# Main.net
KiCad netlist of a schematic drawn in Altium Designer
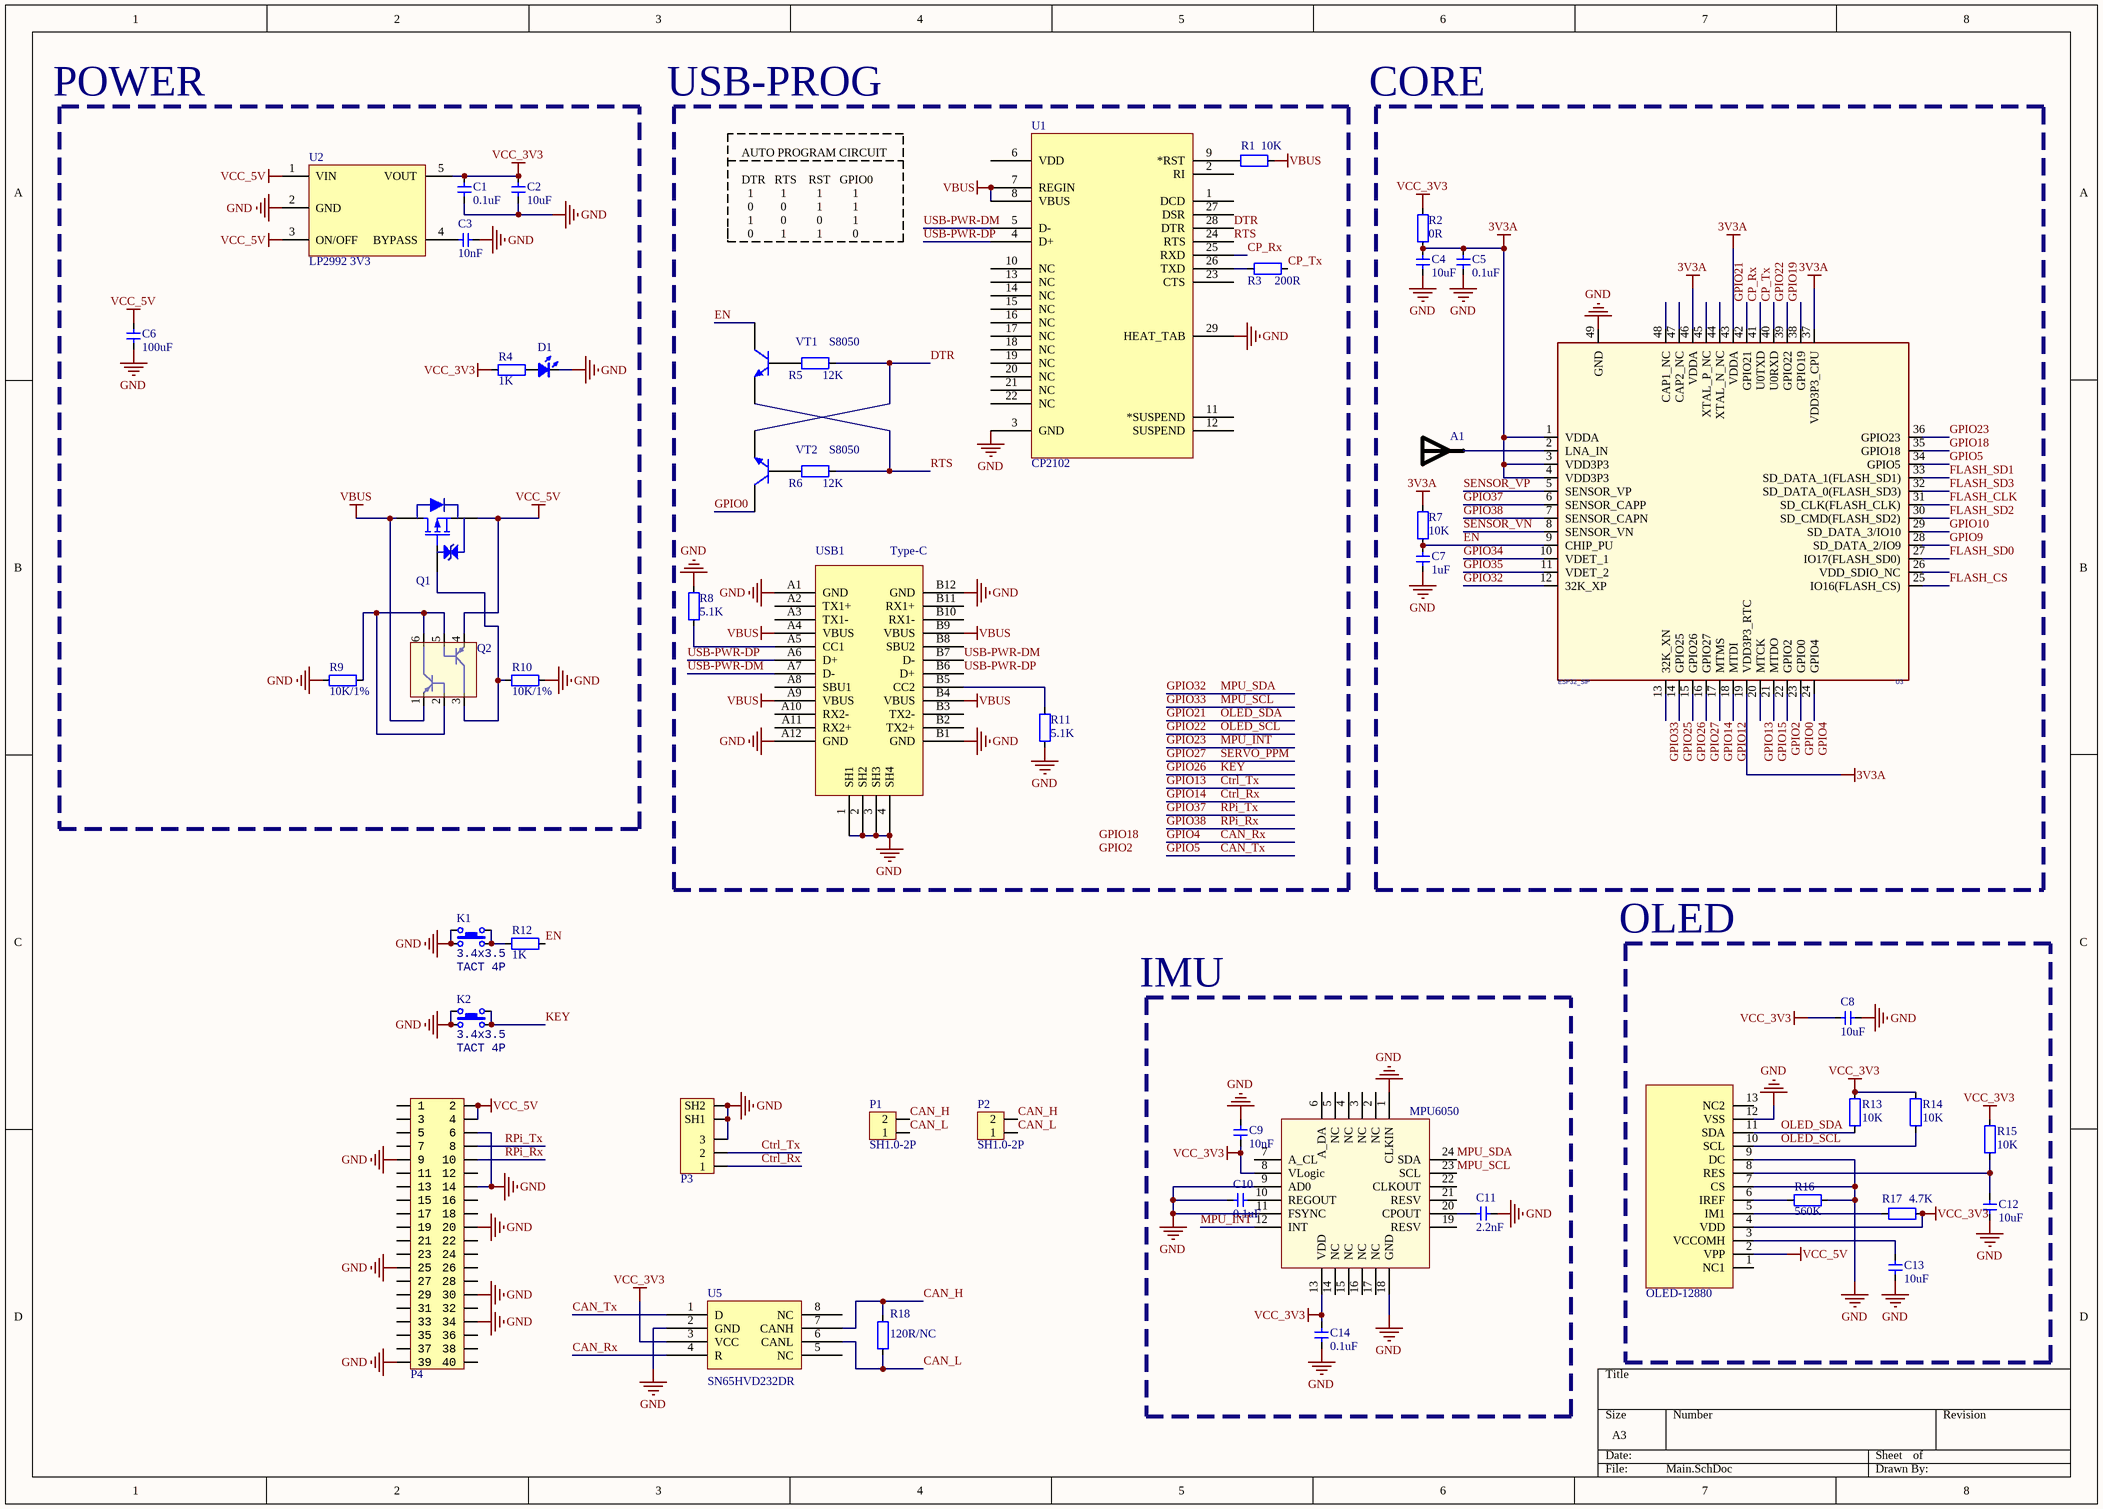
[diagram p0: Main.SchDoc]

(export (version "E")
  (design (tool "Eeschema 10.0.6"))
  (components
    (comp (ref "1")
      (value "OLED-12880")
      (footprint "OLED-12880")
      (libsource (lib "mLib") (part "OLED-12880"))
    )
    (comp (ref "A1")
      (value "RAINSUN")
      (footprint "ANT-Rainsun-AN5120")
      (libsource (lib "MyPcbLib") (part "ANT-Rainsun-AP5120"))
    )
    (comp (ref "C1")
      (value "0.1uF")
      (footprint "CAP_0402")
      (description "Capacitor")
      (libsource (lib "MyPcbLib") (part "电容-0402"))
    )
    (comp (ref "C2")
      (value "10uF")
      (footprint "CAP_0402")
      (description "Capacitor")
      (libsource (lib "MyPcbLib") (part "电容-0402"))
    )
    (comp (ref "C3")
      (value "10nF")
      (footprint "CAP_0402")
      (description "Capacitor")
      (libsource (lib "MyPcbLib") (part "电容-0402"))
    )
    (comp (ref "C4")
      (value "10uF")
      (footprint "CAP_0402")
      (description "Capacitor")
      (libsource (lib "MyPcbLib") (part "电容-0402"))
    )
    (comp (ref "C5")
      (value "0.1uF")
      (footprint "CAP_0402")
      (description "Capacitor")
      (libsource (lib "MyPcbLib") (part "电容-0402"))
    )
    (comp (ref "C6")
      (value "100uF")
      (footprint "1206-CAP")
      (description "Capacitor")
      (libsource (lib "MyPcbLib") (part "电容-1206"))
    )
    (comp (ref "C7")
      (value "1uF")
      (footprint "CAP_0402")
      (description "Capacitor")
      (libsource (lib "MyPcbLib") (part "电容-0402"))
    )
    (comp (ref "C8")
      (value "10uF")
      (footprint "CAP_0402")
      (description "Capacitor")
      (libsource (lib "MyPcbLib") (part "电容-0402"))
    )
    (comp (ref "C9")
      (value "10nF")
      (footprint "CAP_0402")
      (description "Capacitor")
      (libsource (lib "MyPcbLib") (part "电容-0402"))
    )
    (comp (ref "C10")
      (value "0.1uF")
      (footprint "CAP_0402")
      (description "Capacitor")
      (libsource (lib "MyPcbLib") (part "电容-0402"))
    )
    (comp (ref "C11")
      (value "2.2nF")
      (footprint "CAP_0402")
      (description "Capacitor")
      (libsource (lib "MyPcbLib") (part "电容-0402"))
    )
    (comp (ref "C12")
      (value "10uF")
      (footprint "CAP_0402")
      (description "Capacitor")
      (libsource (lib "MyPcbLib") (part "电容-0402"))
    )
    (comp (ref "C13")
      (value "10uF")
      (footprint "CAP_0402")
      (description "Capacitor")
      (libsource (lib "MyPcbLib") (part "电容-0402"))
    )
    (comp (ref "C14")
      (value "0.1uF")
      (footprint "CAP_0402")
      (description "Capacitor")
      (libsource (lib "MyPcbLib") (part "电容-0402"))
    )
    (comp (ref "D1")
      (value "color?")
      (footprint "LED_0402_RED")
      (description "LED")
      (libsource (lib "KitSprout") (part "LED_0402"))
    )
    (comp (ref "K1")
      (value "3.4x3.5")
      (footprint "ButtonTACT_3.5*3.55_90")
      (description "Button")
      (fields (field (name "TYPE") "TACT 4P") (field (name "Comment") "TACT 4P"))
      (libsource (lib "KitSprout") (part "ButtonTACT"))
    )
    (comp (ref "K2")
      (value "3.4x3.5")
      (footprint "ButtonTACT_3.5*3.55_90")
      (description "Button")
      (fields (field (name "TYPE") "TACT 4P") (field (name "Comment") "TACT 4P"))
      (libsource (lib "KitSprout") (part "ButtonTACT"))
    )
    (comp (ref "P1") (value "SH1.0-2P") (footprint "SH1.0-2P") (libsource (lib "MyPcbLib") (part "SH1.0-2P")))
    (comp (ref "P2") (value "SH1.0-2P") (footprint "SH1.0-2P") (libsource (lib "MyPcbLib") (part "SH1.0-2P")))
    (comp (ref "P3")
      (value "SH1.0-3P")
      (footprint "SH1.0-3P")
      (description "Header")
      (libsource (lib "MyPcbLib") (part "SH1.0-3P"))
    )
    (comp (ref "P4")
      (value "HDR2x20_2.54")
      (footprint "HDR2X20_2.54_180F")
      (description "Header")
      (libsource (lib "KitSprout") (part "HDR2x20_2.54"))
    )
    (comp (ref "Q1")
      (value "AO3415A")
      (footprint "SOT23-3")
      (description "MOSFET")
      (fields (field (name "PUBLISHER") "Altium Limited"))
      (libsource (lib "MyPcbLib") (part "AO3415A"))
    )
    (comp (ref "Q2")
      (value "BCM856BS")
      (footprint "SOT363-6")
      (description "Transistor")
      (libsource (lib "MyPcbLib") (part "BCM856BS"))
    )
    (comp (ref "R1")
      (value "10K")
      (footprint "RES_0402")
      (description "Resistor")
      (libsource (lib "") (part "电阻-0402_3"))
    )
    (comp (ref "R2")
      (value "0R")
      (footprint "RES_0402")
      (description "Resistor")
      (libsource (lib "") (part "电阻-0402_2"))
    )
    (comp (ref "R3")
      (value "200R")
      (footprint "RES_0402")
      (description "Resistor")
      (libsource (lib "") (part "电阻-0402_3"))
    )
    (comp (ref "R4")
      (value "1K")
      (footprint "RES_0402")
      (description "Resistor")
      (libsource (lib "") (part "电阻-0402_1"))
    )
    (comp (ref "R5")
      (value "12K")
      (footprint "RES_0402")
      (description "Resistor")
      (libsource (lib "") (part "电阻-0402_3"))
    )
    (comp (ref "R6")
      (value "12K")
      (footprint "RES_0402")
      (description "Resistor")
      (libsource (lib "") (part "电阻-0402_3"))
    )
    (comp (ref "R7")
      (value "10K")
      (footprint "RES_0402")
      (description "Resistor")
      (libsource (lib "") (part "电阻-0402_2"))
    )
    (comp (ref "R8")
      (value "5.1K")
      (footprint "RES_0402")
      (description "Resistor")
      (libsource (lib "") (part "电阻-0402_2"))
    )
    (comp (ref "R9")
      (value "10K/1%")
      (footprint "RES_0402")
      (description "Resistor")
      (libsource (lib "") (part "电阻-0402_1"))
    )
    (comp (ref "R10")
      (value "10K/1%")
      (footprint "RES_0402")
      (description "Resistor")
      (libsource (lib "") (part "电阻-0402_1"))
    )
    (comp (ref "R11")
      (value "5.1K")
      (footprint "RES_0402")
      (description "Resistor")
      (libsource (lib "MyPcbLib") (part "电阻-0402"))
    )
    (comp (ref "R12")
      (value "1K")
      (footprint "RES_0402")
      (description "Resistor")
      (libsource (lib "") (part "电阻-0402_1"))
    )
    (comp (ref "R13")
      (value "10K")
      (footprint "RES_0402")
      (description "Resistor")
      (libsource (lib "MyPcbLib") (part "电阻-0402"))
    )
    (comp (ref "R14")
      (value "10K")
      (footprint "RES_0402")
      (description "Resistor")
      (libsource (lib "MyPcbLib") (part "电阻-0402"))
    )
    (comp (ref "R15")
      (value "10K")
      (footprint "RES_0402")
      (description "Resistor")
      (libsource (lib "MyPcbLib") (part "电阻-0402"))
    )
    (comp (ref "R16")
      (value "560K")
      (footprint "RES_0402")
      (description "Resistor")
      (libsource (lib "") (part "电阻-0402_1"))
    )
    (comp (ref "R17")
      (value "4.7K")
      (footprint "RES_0402")
      (description "Resistor")
      (libsource (lib "") (part "电阻-0402_1"))
    )
    (comp (ref "R18")
      (value "120R/NC")
      (footprint "RES_0402")
      (description "Resistor")
      (libsource (lib "") (part "电阻-0402_2"))
    )
    (comp (ref "U1")
      (value "CP2102")
      (footprint "QFN-28")
      (description "USB转TTL")
      (libsource (lib "mLib") (part "CP2102"))
    )
    (comp (ref "U2")
      (value "LP2992 3V3")
      (footprint "SOT23-5")
      (description "LDO")
      (libsource (lib "MyPcbLib") (part "LP2992"))
    )
    (comp (ref "U3")
      (value "ESP32_SIP")
      (footprint "QFN-48_7X7")
      (libsource (lib "MyPcbLib") (part "ESP32-PICO"))
    )
    (comp (ref "U4")
      (value "MPU6050")
      (footprint "QFN-24")
      (description "六轴传感器")
      (libsource (lib "mLib") (part "MPU6050"))
    )
    (comp (ref "U5")
      (value "SN65HVD232D")
      (footprint "SO-8")
      (fields
        (field (name "MANUFACTURER") "Texas Instruments")
        (field (name "MANUFACTURER PART NUMBER") "SN65HVD232DR")
      )
      (libsource (lib "MyPcbLib") (part "SN65HVD232D"))
    )
    (comp (ref "USB1")
      (value "Type-C")
      (footprint "Type-C-TOP")
      (libsource (lib "MyPcbLib") (part "USB-Type-C-TOP"))
    )
    (comp (ref "VT1")
      (value "S8050")
      (footprint "SMT_TRIODE_NPN")
      (description "Surface mount NPN transistor, package SOT-23")
      (libsource (lib "MyPcbLib") (part "SMT_TRIODE_NPN"))
    )
    (comp (ref "VT2")
      (value "S8050")
      (footprint "SMT_TRIODE_NPN")
      (description "Surface mount NPN transistor, package SOT-23")
      (libsource (lib "MyPcbLib") (part "SMT_TRIODE_NPN"))
    )
  )
  (nets
    (net (code "1") (name "/CAN_H") (class "Default")
      (node (ref "P1") (pin "2") (pinfunction "2_2") (pintype "passive"))
      (node (ref "P2") (pin "2") (pinfunction "2_2") (pintype "passive"))
      (node (ref "R18") (pin "1") (pinfunction "1_1") (pintype "passive"))
      (node (ref "U5") (pin "7") (pinfunction "CANH_7") (pintype "passive"))
    )
    (net (code "2") (name "/CAN_L") (class "Default")
      (node (ref "P1") (pin "1") (pinfunction "1_1") (pintype "passive"))
      (node (ref "P2") (pin "1") (pinfunction "1_1") (pintype "passive"))
      (node (ref "R18") (pin "2") (pinfunction "2_2") (pintype "passive"))
      (node (ref "U5") (pin "6") (pinfunction "CANL_6") (pintype "passive"))
    )
    (net (code "3") (name "/CAN_Rx") (class "Default")
      (node (ref "U3") (pin "24") (pinfunction "GPIO4_24") (pintype "passive"))
      (node (ref "U5") (pin "4") (pinfunction "R_4") (pintype "passive"))
    )
    (net (code "4") (name "/CAN_Tx") (class "Default")
      (node (ref "U3") (pin "34") (pinfunction "GPIO5_34") (pintype "passive"))
      (node (ref "U5") (pin "1") (pinfunction "D_1") (pintype "passive"))
    )
    (net (code "5") (name "/CP_Rx") (class "Default")
      (node (ref "U1") (pin "25") (pinfunction "RXD_25") (pintype "passive"))
      (node (ref "U3") (pin "41") (pinfunction "U0TXD_41") (pintype "power_in"))
    )
    (net (code "6") (name "/CP_Tx") (class "Default")
      (node (ref "R3") (pin "1") (pinfunction "1_1") (pintype "passive"))
      (node (ref "U3") (pin "40") (pinfunction "U0RXD_40") (pintype "power_in"))
    )
    (net (code "7") (name "/Ctrl_Rx") (class "Default")
      (node (ref "P3") (pin "1") (pinfunction "1_1") (pintype "passive"))
      (node (ref "U3") (pin "17") (pinfunction "MTMS_17") (pintype "passive"))
    )
    (net (code "8") (name "/Ctrl_Tx") (class "Default")
      (node (ref "P3") (pin "2") (pinfunction "2_2") (pintype "passive"))
      (node (ref "U3") (pin "20") (pinfunction "MTCK_20") (pintype "passive"))
    )
    (net (code "9") (name "/DTR") (class "Default")
      (node (ref "R5") (pin "1") (pinfunction "1_1") (pintype "passive"))
      (node (ref "U1") (pin "28") (pinfunction "DTR_28") (pintype "passive"))
      (node (ref "VT2") (pin "2") (pinfunction "E_2") (pintype "passive"))
    )
    (net (code "10") (name "/EN") (class "Default")
      (node (ref "C7") (pin "1") (pinfunction "1_1") (pintype "passive"))
      (node (ref "R12") (pin "2") (pinfunction "2_2") (pintype "passive"))
      (node (ref "R7") (pin "2") (pinfunction "2_2") (pintype "passive"))
      (node (ref "U3") (pin "9") (pinfunction "CHIP_PU_9") (pintype "passive"))
      (node (ref "VT1") (pin "3") (pinfunction "C_3") (pintype "passive"))
    )
    (net (code "11") (name "/FLASH_CLK") (class "Default")
      (node (ref "U3") (pin "31") (pinfunction "SD_CLK(FLASH_CLK)_31") (pintype "passive"))
    )
    (net (code "12") (name "/FLASH_CS") (class "Default")
      (node (ref "U3") (pin "25") (pinfunction "IO16(FLASH_CS)_25") (pintype "passive"))
    )
    (net (code "13") (name "/FLASH_SD0") (class "Default")
      (node (ref "U3") (pin "27") (pinfunction "IO17(FLASH_SD0)_27") (pintype "passive"))
    )
    (net (code "14") (name "/FLASH_SD1") (class "Default")
      (node (ref "U3") (pin "33") (pinfunction "SD_DATA_1(FLASH_SD1)_33") (pintype "passive"))
    )
    (net (code "15") (name "/FLASH_SD2") (class "Default")
      (node (ref "U3") (pin "30") (pinfunction "SD_CMD(FLASH_SD2)_30") (pintype "passive"))
    )
    (net (code "16") (name "/FLASH_SD3") (class "Default")
      (node (ref "U3") (pin "32") (pinfunction "SD_DATA_0(FLASH_SD3)_32") (pintype "passive"))
    )
    (net (code "17") (name "/GPIO0") (class "Default")
      (node (ref "U3") (pin "23") (pinfunction "GPIO0_23") (pintype "passive"))
      (node (ref "VT2") (pin "3") (pinfunction "C_3") (pintype "passive"))
    )
    (net (code "18") (name "/GPIO2") (class "Default")
      (node (ref "U3") (pin "22") (pinfunction "GPIO2_22") (pintype "passive"))
    )
    (net (code "19") (name "/GPIO9") (class "Default")
      (node (ref "U3") (pin "28") (pinfunction "SD_DATA_2/IO9_28") (pintype "passive"))
    )
    (net (code "20") (name "/GPIO10") (class "Default")
      (node (ref "U3") (pin "29") (pinfunction "SD_DATA_3/IO10_29") (pintype "passive"))
    )
    (net (code "21") (name "/GPIO12") (class "Default")
      (node (ref "U3") (pin "18") (pinfunction "MTDI_18") (pintype "passive"))
    )
    (net (code "22") (name "/GPIO15") (class "Default")
      (node (ref "U3") (pin "21") (pinfunction "MTDO_21") (pintype "passive"))
    )
    (net (code "23") (name "/GPIO18") (class "Default")
      (node (ref "U3") (pin "35") (pinfunction "GPIO18_35") (pintype "passive"))
    )
    (net (code "24") (name "/GPIO19") (class "Default")
      (node (ref "U3") (pin "38") (pinfunction "GPIO19_38") (pintype "passive"))
    )
    (net (code "25") (name "/GPIO21") (class "Default")
      (node (ref "1") (pin "11") (pinfunction "SDA_11") (pintype "passive"))
      (node (ref "R13") (pin "1") (pinfunction "1_1") (pintype "passive"))
      (node (ref "U3") (pin "42") (pinfunction "GPIO21_42") (pintype "passive"))
    )
    (net (code "26") (name "/GPIO22") (class "Default")
      (node (ref "1") (pin "10") (pinfunction "SCL_10") (pintype "passive"))
      (node (ref "R14") (pin "1") (pinfunction "1_1") (pintype "passive"))
      (node (ref "U3") (pin "39") (pinfunction "GPIO22_39") (pintype "passive"))
    )
    (net (code "27") (name "/GPIO23") (class "Default")
      (node (ref "U3") (pin "36") (pinfunction "GPIO23_36") (pintype "passive"))
      (node (ref "U4") (pin "12") (pinfunction "INT_12") (pintype "passive"))
    )
    (net (code "28") (name "/GPIO25") (class "Default")
      (node (ref "U3") (pin "14") (pinfunction "GPIO25_14") (pintype "passive"))
    )
    (net (code "29") (name "/GPIO26") (class "Default")
      (node (ref "K2") (pin "2") (pinfunction "2_2") (pintype "passive"))
      (node (ref "K2") (pin "4") (pinfunction "4_4") (pintype "passive"))
      (node (ref "U3") (pin "15") (pinfunction "GPIO26_15") (pintype "passive"))
    )
    (net (code "30") (name "/GPIO27") (class "Default")
      (node (ref "U3") (pin "16") (pinfunction "GPIO27_16") (pintype "passive"))
    )
    (net (code "31") (name "/GPIO32") (class "Default")
      (node (ref "U3") (pin "12") (pinfunction "32K_XP_12") (pintype "passive"))
      (node (ref "U4") (pin "24") (pinfunction "SDA_24") (pintype "passive"))
    )
    (net (code "32") (name "/GPIO33") (class "Default")
      (node (ref "U3") (pin "13") (pinfunction "32K_XN_13") (pintype "passive"))
      (node (ref "U4") (pin "23") (pinfunction "SCL_23") (pintype "passive"))
    )
    (net (code "33") (name "/GPIO34") (class "Default")
      (node (ref "U3") (pin "10") (pinfunction "VDET_1_10") (pintype "passive"))
    )
    (net (code "34") (name "/GPIO35") (class "Default")
      (node (ref "U3") (pin "11") (pinfunction "VDET_2_11") (pintype "passive"))
    )
    (net (code "35") (name "/GPIO37") (class "Default")
      (node (ref "P4") (pin "8") (pinfunction "8_8") (pintype "passive"))
      (node (ref "U3") (pin "6") (pinfunction "SENSOR_CAPP_6") (pintype "passive"))
    )
    (net (code "36") (name "/GPIO38") (class "Default")
      (node (ref "P4") (pin "10") (pinfunction "10_10") (pintype "passive"))
      (node (ref "U3") (pin "7") (pinfunction "SENSOR_CAPN_7") (pintype "passive"))
    )
    (net (code "37") (name "/RTS") (class "Default")
      (node (ref "R6") (pin "1") (pinfunction "1_1") (pintype "passive"))
      (node (ref "U1") (pin "24") (pinfunction "RTS_24") (pintype "passive"))
      (node (ref "VT1") (pin "2") (pinfunction "E_2") (pintype "passive"))
    )
    (net (code "38") (name "/SENSOR_VN") (class "Default")
      (node (ref "U3") (pin "8") (pinfunction "SENSOR_VN_8") (pintype "passive"))
    )
    (net (code "39") (name "/SENSOR_VP") (class "Default")
      (node (ref "U3") (pin "5") (pinfunction "SENSOR_VP_5") (pintype "passive"))
    )
    (net (code "40") (name "/USB-PWR-DM") (class "Default")
      (node (ref "U1") (pin "5") (pinfunction "D-_5") (pintype "passive"))
      (node (ref "USB1") (pin "A7") (pinfunction "D-_A7") (pintype "passive"))
      (node (ref "USB1") (pin "B7") (pinfunction "D-_B7") (pintype "passive"))
    )
    (net (code "41") (name "/USB-PWR-DP") (class "Default")
      (node (ref "U1") (pin "4") (pinfunction "D+_4") (pintype "passive"))
      (node (ref "USB1") (pin "A6") (pinfunction "D+_A6") (pintype "passive"))
      (node (ref "USB1") (pin "B6") (pinfunction "D+_B6") (pintype "passive"))
    )
    (net (code "42") (name "3V3A") (class "Default")
      (node (ref "C4") (pin "2") (pinfunction "2_2") (pintype "passive"))
      (node (ref "C5") (pin "2") (pinfunction "2_2") (pintype "passive"))
      (node (ref "R2") (pin "2") (pinfunction "2_2") (pintype "passive"))
      (node (ref "R7") (pin "1") (pinfunction "1_1") (pintype "passive"))
      (node (ref "U3") (pin "1") (pinfunction "VDDA_1") (pintype "power_in"))
      (node (ref "U3") (pin "19") (pinfunction "VDD3P3_RTC_19") (pintype "power_in"))
      (node (ref "U3") (pin "3") (pinfunction "VDD3P3_3") (pintype "power_in"))
      (node (ref "U3") (pin "37") (pinfunction "VDD3P3_CPU_37") (pintype "power_in"))
      (node (ref "U3") (pin "4") (pinfunction "VDD3P3_4") (pintype "power_in"))
      (node (ref "U3") (pin "43") (pinfunction "VDDA_43") (pintype "power_in"))
      (node (ref "U3") (pin "46") (pinfunction "VDDA_46") (pintype "power_in"))
    )
    (net (code "43") (name "GND") (class "Default")
      (node (ref "1") (pin "12") (pinfunction "VSS_12") (pintype "passive"))
      (node (ref "1") (pin "7") (pinfunction "CS_7") (pintype "passive"))
      (node (ref "1") (pin "9") (pinfunction "DC_9") (pintype "passive"))
      (node (ref "C1") (pin "1") (pinfunction "1_1") (pintype "passive"))
      (node (ref "C10") (pin "2") (pinfunction "2_2") (pintype "passive"))
      (node (ref "C11") (pin "1") (pinfunction "1_1") (pintype "passive"))
      (node (ref "C12") (pin "1") (pinfunction "1_1") (pintype "passive"))
      (node (ref "C13") (pin "1") (pinfunction "1_1") (pintype "passive"))
      (node (ref "C14") (pin "1") (pinfunction "1_1") (pintype "passive"))
      (node (ref "C2") (pin "1") (pinfunction "1_1") (pintype "passive"))
      (node (ref "C3") (pin "1") (pinfunction "1_1") (pintype "passive"))
      (node (ref "C4") (pin "1") (pinfunction "1_1") (pintype "passive"))
      (node (ref "C5") (pin "1") (pinfunction "1_1") (pintype "passive"))
      (node (ref "C6") (pin "1") (pinfunction "1_1") (pintype "passive"))
      (node (ref "C7") (pin "2") (pinfunction "2_2") (pintype "passive"))
      (node (ref "C8") (pin "1") (pinfunction "1_1") (pintype "passive"))
      (node (ref "C9") (pin "2") (pinfunction "2_2") (pintype "passive"))
      (node (ref "D1") (pin "2") (pinfunction "K_2") (pintype "passive"))
      (node (ref "K1") (pin "1") (pinfunction "1_1") (pintype "passive"))
      (node (ref "K1") (pin "3") (pinfunction "3_3") (pintype "passive"))
      (node (ref "K2") (pin "1") (pinfunction "1_1") (pintype "passive"))
      (node (ref "K2") (pin "3") (pinfunction "3_3") (pintype "passive"))
      (node (ref "P3") (pin "3") (pinfunction "3_3") (pintype "passive"))
      (node (ref "P3") (pin "SH1") (pinfunction "SH1_SH1") (pintype "passive"))
      (node (ref "P3") (pin "SH2") (pinfunction "SH2_SH2") (pintype "passive"))
      (node (ref "P4") (pin "14") (pinfunction "14_14") (pintype "passive"))
      (node (ref "P4") (pin "20") (pinfunction "20_20") (pintype "passive"))
      (node (ref "P4") (pin "25") (pinfunction "25_25") (pintype "passive"))
      (node (ref "P4") (pin "30") (pinfunction "30_30") (pintype "passive"))
      (node (ref "P4") (pin "34") (pinfunction "34_34") (pintype "passive"))
      (node (ref "P4") (pin "39") (pinfunction "39_39") (pintype "passive"))
      (node (ref "P4") (pin "6") (pinfunction "6_6") (pintype "passive"))
      (node (ref "P4") (pin "9") (pinfunction "9_9") (pintype "passive"))
      (node (ref "R10") (pin "2") (pinfunction "2_2") (pintype "passive"))
      (node (ref "R11") (pin "1") (pinfunction "1_1") (pintype "passive"))
      (node (ref "R16") (pin "2") (pinfunction "2_2") (pintype "passive"))
      (node (ref "R8") (pin "1") (pinfunction "1_1") (pintype "passive"))
      (node (ref "R9") (pin "1") (pinfunction "1_1") (pintype "passive"))
      (node (ref "U1") (pin "29") (pinfunction "HEAT_TAB_29") (pintype "passive"))
      (node (ref "U1") (pin "3") (pinfunction "GND_3") (pintype "passive"))
      (node (ref "U2") (pin "2") (pinfunction "GND_2") (pintype "passive"))
      (node (ref "U3") (pin "49") (pinfunction "GND_49") (pintype "power_in"))
      (node (ref "U4") (pin "1") (pinfunction "CLKIN_1") (pintype "passive"))
      (node (ref "U4") (pin "11") (pinfunction "FSYNC_11") (pintype "passive"))
      (node (ref "U4") (pin "18") (pinfunction "GND_18") (pintype "passive"))
      (node (ref "U4") (pin "9") (pinfunction "AD0_9") (pintype "passive"))
      (node (ref "U5") (pin "2") (pinfunction "GND_2") (pintype "passive"))
      (node (ref "USB1") (pin "1") (pinfunction "SH1_1") (pintype "passive"))
      (node (ref "USB1") (pin "2") (pinfunction "SH2_2") (pintype "passive"))
      (node (ref "USB1") (pin "3") (pinfunction "SH3_3") (pintype "passive"))
      (node (ref "USB1") (pin "4") (pinfunction "SH4_4") (pintype "passive"))
      (node (ref "USB1") (pin "A1") (pinfunction "GND_A1") (pintype "passive"))
      (node (ref "USB1") (pin "A12") (pinfunction "GND_A12") (pintype "passive"))
      (node (ref "USB1") (pin "B1") (pinfunction "GND_B1") (pintype "passive"))
      (node (ref "USB1") (pin "B12") (pinfunction "GND_B12") (pintype "passive"))
    )
    (net (code "44") (name "Net-(1-IM1)") (class "Default")
      (node (ref "1") (pin "5") (pinfunction "IM1_5") (pintype "passive"))
      (node (ref "R17") (pin "1") (pinfunction "1_1") (pintype "passive"))
    )
    (net (code "45") (name "Net-(1-IREF)") (class "Default")
      (node (ref "1") (pin "6") (pinfunction "IREF_6") (pintype "passive"))
      (node (ref "R16") (pin "1") (pinfunction "1_1") (pintype "passive"))
    )
    (net (code "46") (name "Net-(1-RES)") (class "Default")
      (node (ref "1") (pin "8") (pinfunction "RES_8") (pintype "passive"))
      (node (ref "C12") (pin "2") (pinfunction "2_2") (pintype "passive"))
      (node (ref "R15") (pin "1") (pinfunction "1_1") (pintype "passive"))
    )
    (net (code "47") (name "Net-(1-VCCOMH)") (class "Default")
      (node (ref "1") (pin "3") (pinfunction "VCCOMH_3") (pintype "passive"))
      (node (ref "C13") (pin "2") (pinfunction "2_2") (pintype "passive"))
    )
    (net (code "48") (name "Net-(D1-A)") (class "Default")
      (node (ref "D1") (pin "1") (pinfunction "A_1") (pintype "passive"))
      (node (ref "R4") (pin "2") (pinfunction "2_2") (pintype "passive"))
    )
    (net (code "49") (name "Net-(K1-Pad2)") (class "Default")
      (node (ref "K1") (pin "2") (pinfunction "2_2") (pintype "passive"))
      (node (ref "K1") (pin "4") (pinfunction "4_4") (pintype "passive"))
      (node (ref "R12") (pin "1") (pinfunction "1_1") (pintype "passive"))
    )
    (net (code "50") (name "Net-(Q1-G)") (class "Default")
      (node (ref "Q1") (pin "1") (pinfunction "G_1") (pintype "passive"))
      (node (ref "Q2") (pin "3") (pintype "passive"))
      (node (ref "R10") (pin "1") (pinfunction "1_1") (pintype "passive"))
    )
    (net (code "51") (name "Net-(Q2-Pad2)") (class "Default")
      (node (ref "Q2") (pin "2") (pintype "passive"))
      (node (ref "Q2") (pin "5") (pintype "passive"))
      (node (ref "Q2") (pin "6") (pintype "passive"))
      (node (ref "R9") (pin "2") (pinfunction "2_2") (pintype "passive"))
    )
    (net (code "52") (name "Net-(U1-*RST)") (class "Default")
      (node (ref "R1") (pin "2") (pinfunction "2_2") (pintype "passive"))
      (node (ref "U1") (pin "9") (pinfunction "*RST_9") (pintype "passive"))
    )
    (net (code "53") (name "Net-(U1-TXD)") (class "Default")
      (node (ref "R3") (pin "2") (pinfunction "2_2") (pintype "passive"))
      (node (ref "U1") (pin "26") (pinfunction "TXD_26") (pintype "passive"))
    )
    (net (code "54") (name "Net-(U2-BYPASS)") (class "Default")
      (node (ref "C3") (pin "2") (pinfunction "2_2") (pintype "passive"))
      (node (ref "U2") (pin "4") (pinfunction "BYPASS_4") (pintype "passive"))
    )
    (net (code "55") (name "Net-(U3-LNA_IN)") (class "Default")
      (node (ref "A1") (pin "1") (pinfunction "1_1") (pintype "passive"))
      (node (ref "U3") (pin "2") (pinfunction "LNA_IN_2") (pintype "passive"))
    )
    (net (code "56") (name "Net-(U4-CPOUT)") (class "Default")
      (node (ref "C11") (pin "2") (pinfunction "2_2") (pintype "passive"))
      (node (ref "U4") (pin "20") (pinfunction "CPOUT_20") (pintype "passive"))
    )
    (net (code "57") (name "Net-(U4-REGOUT)") (class "Default")
      (node (ref "C10") (pin "1") (pinfunction "1_1") (pintype "passive"))
      (node (ref "U4") (pin "10") (pinfunction "REGOUT_10") (pintype "passive"))
    )
    (net (code "58") (name "Net-(USB1-CC1)") (class "Default")
      (node (ref "R8") (pin "2") (pinfunction "2_2") (pintype "passive"))
      (node (ref "USB1") (pin "A5") (pinfunction "CC1_A5") (pintype "passive"))
    )
    (net (code "59") (name "Net-(USB1-CC2)") (class "Default")
      (node (ref "R11") (pin "2") (pinfunction "2_2") (pintype "passive"))
      (node (ref "USB1") (pin "B5") (pinfunction "CC2_B5") (pintype "passive"))
    )
    (net (code "60") (name "Net-(VT1-B)") (class "Default")
      (node (ref "R5") (pin "2") (pinfunction "2_2") (pintype "passive"))
      (node (ref "VT1") (pin "1") (pinfunction "B_1") (pintype "passive"))
    )
    (net (code "61") (name "Net-(VT2-B)") (class "Default")
      (node (ref "R6") (pin "2") (pinfunction "2_2") (pintype "passive"))
      (node (ref "VT2") (pin "1") (pinfunction "B_1") (pintype "passive"))
    )
    (net (code "62") (name "VBUS") (class "Default")
      (node (ref "Q1") (pin "3") (pinfunction "D_3") (pintype "passive"))
      (node (ref "Q2") (pin "1") (pintype "passive"))
      (node (ref "R1") (pin "1") (pinfunction "1_1") (pintype "passive"))
      (node (ref "U1") (pin "7") (pinfunction "REGIN_7") (pintype "passive"))
      (node (ref "U1") (pin "8") (pinfunction "VBUS_8") (pintype "passive"))
      (node (ref "USB1") (pin "A4") (pinfunction "VBUS_A4") (pintype "passive"))
      (node (ref "USB1") (pin "A9") (pinfunction "VBUS_A9") (pintype "passive"))
      (node (ref "USB1") (pin "B4") (pinfunction "VBUS_B4") (pintype "passive"))
      (node (ref "USB1") (pin "B9") (pinfunction "VBUS_B9") (pintype "passive"))
    )
    (net (code "63") (name "VCC_3V3") (class "Default")
      (node (ref "1") (pin "4") (pinfunction "VDD_4") (pintype "passive"))
      (node (ref "C1") (pin "2") (pinfunction "2_2") (pintype "passive"))
      (node (ref "C14") (pin "2") (pinfunction "2_2") (pintype "passive"))
      (node (ref "C2") (pin "2") (pinfunction "2_2") (pintype "passive"))
      (node (ref "C8") (pin "2") (pinfunction "2_2") (pintype "passive"))
      (node (ref "C9") (pin "1") (pinfunction "1_1") (pintype "passive"))
      (node (ref "R13") (pin "2") (pinfunction "2_2") (pintype "passive"))
      (node (ref "R14") (pin "2") (pinfunction "2_2") (pintype "passive"))
      (node (ref "R15") (pin "2") (pinfunction "2_2") (pintype "passive"))
      (node (ref "R17") (pin "2") (pinfunction "2_2") (pintype "passive"))
      (node (ref "R2") (pin "1") (pinfunction "1_1") (pintype "passive"))
      (node (ref "R4") (pin "1") (pinfunction "1_1") (pintype "passive"))
      (node (ref "U2") (pin "5") (pinfunction "VOUT_5") (pintype "passive"))
      (node (ref "U4") (pin "13") (pinfunction "VDD_13") (pintype "passive"))
      (node (ref "U4") (pin "8") (pinfunction "VLogic_8") (pintype "passive"))
      (node (ref "U5") (pin "3") (pinfunction "VCC_3") (pintype "passive"))
    )
    (net (code "64") (name "VCC_5V") (class "Default")
      (node (ref "1") (pin "2") (pinfunction "VPP_2") (pintype "passive"))
      (node (ref "C6") (pin "2") (pinfunction "2_2") (pintype "passive"))
      (node (ref "P4") (pin "2") (pinfunction "2_2") (pintype "passive"))
      (node (ref "P4") (pin "4") (pinfunction "4_4") (pintype "passive"))
      (node (ref "Q1") (pin "2") (pinfunction "S_2") (pintype "passive"))
      (node (ref "Q2") (pin "4") (pintype "passive"))
      (node (ref "U2") (pin "1") (pinfunction "VIN_1") (pintype "passive"))
      (node (ref "U2") (pin "3") (pinfunction "ON/OFF_3") (pintype "passive"))
    )
    (net (code "65") (name "unconnected-(1-NC1-Pad1)") (class "Default")
      (node (ref "1") (pin "1") (pinfunction "NC1_1") (pintype "passive"))
    )
    (net (code "66") (name "unconnected-(1-NC2-Pad13)") (class "Default")
      (node (ref "1") (pin "13") (pinfunction "NC2_13") (pintype "passive"))
    )
    (net (code "67") (name "unconnected-(P4-Pad1)") (class "Default")
      (node (ref "P4") (pin "1") (pinfunction "1_1") (pintype "passive"))
    )
    (net (code "68") (name "unconnected-(P4-Pad3)") (class "Default")
      (node (ref "P4") (pin "3") (pinfunction "3_3") (pintype "passive"))
    )
    (net (code "69") (name "unconnected-(P4-Pad5)") (class "Default")
      (node (ref "P4") (pin "5") (pinfunction "5_5") (pintype "passive"))
    )
    (net (code "70") (name "unconnected-(P4-Pad7)") (class "Default")
      (node (ref "P4") (pin "7") (pinfunction "7_7") (pintype "passive"))
    )
    (net (code "71") (name "unconnected-(P4-Pad11)") (class "Default")
      (node (ref "P4") (pin "11") (pinfunction "11_11") (pintype "passive"))
    )
    (net (code "72") (name "unconnected-(P4-Pad12)") (class "Default")
      (node (ref "P4") (pin "12") (pinfunction "12_12") (pintype "passive"))
    )
    (net (code "73") (name "unconnected-(P4-Pad13)") (class "Default")
      (node (ref "P4") (pin "13") (pinfunction "13_13") (pintype "passive"))
    )
    (net (code "74") (name "unconnected-(P4-Pad15)") (class "Default")
      (node (ref "P4") (pin "15") (pinfunction "15_15") (pintype "passive"))
    )
    (net (code "75") (name "unconnected-(P4-Pad16)") (class "Default")
      (node (ref "P4") (pin "16") (pinfunction "16_16") (pintype "passive"))
    )
    (net (code "76") (name "unconnected-(P4-Pad17)") (class "Default")
      (node (ref "P4") (pin "17") (pinfunction "17_17") (pintype "passive"))
    )
    (net (code "77") (name "unconnected-(P4-Pad18)") (class "Default")
      (node (ref "P4") (pin "18") (pinfunction "18_18") (pintype "passive"))
    )
    (net (code "78") (name "unconnected-(P4-Pad19)") (class "Default")
      (node (ref "P4") (pin "19") (pinfunction "19_19") (pintype "passive"))
    )
    (net (code "79") (name "unconnected-(P4-Pad21)") (class "Default")
      (node (ref "P4") (pin "21") (pinfunction "21_21") (pintype "passive"))
    )
    (net (code "80") (name "unconnected-(P4-Pad22)") (class "Default")
      (node (ref "P4") (pin "22") (pinfunction "22_22") (pintype "passive"))
    )
    (net (code "81") (name "unconnected-(P4-Pad23)") (class "Default")
      (node (ref "P4") (pin "23") (pinfunction "23_23") (pintype "passive"))
    )
    (net (code "82") (name "unconnected-(P4-Pad24)") (class "Default")
      (node (ref "P4") (pin "24") (pinfunction "24_24") (pintype "passive"))
    )
    (net (code "83") (name "unconnected-(P4-Pad26)") (class "Default")
      (node (ref "P4") (pin "26") (pinfunction "26_26") (pintype "passive"))
    )
    (net (code "84") (name "unconnected-(P4-Pad27)") (class "Default")
      (node (ref "P4") (pin "27") (pinfunction "27_27") (pintype "passive"))
    )
    (net (code "85") (name "unconnected-(P4-Pad28)") (class "Default")
      (node (ref "P4") (pin "28") (pinfunction "28_28") (pintype "passive"))
    )
    (net (code "86") (name "unconnected-(P4-Pad29)") (class "Default")
      (node (ref "P4") (pin "29") (pinfunction "29_29") (pintype "passive"))
    )
    (net (code "87") (name "unconnected-(P4-Pad31)") (class "Default")
      (node (ref "P4") (pin "31") (pinfunction "31_31") (pintype "passive"))
    )
    (net (code "88") (name "unconnected-(P4-Pad32)") (class "Default")
      (node (ref "P4") (pin "32") (pinfunction "32_32") (pintype "passive"))
    )
    (net (code "89") (name "unconnected-(P4-Pad33)") (class "Default")
      (node (ref "P4") (pin "33") (pinfunction "33_33") (pintype "passive"))
    )
    (net (code "90") (name "unconnected-(P4-Pad35)") (class "Default")
      (node (ref "P4") (pin "35") (pinfunction "35_35") (pintype "passive"))
    )
    (net (code "91") (name "unconnected-(P4-Pad36)") (class "Default")
      (node (ref "P4") (pin "36") (pinfunction "36_36") (pintype "passive"))
    )
    (net (code "92") (name "unconnected-(P4-Pad37)") (class "Default")
      (node (ref "P4") (pin "37") (pinfunction "37_37") (pintype "passive"))
    )
    (net (code "93") (name "unconnected-(P4-Pad38)") (class "Default")
      (node (ref "P4") (pin "38") (pinfunction "38_38") (pintype "passive"))
    )
    (net (code "94") (name "unconnected-(P4-Pad40)") (class "Default")
      (node (ref "P4") (pin "40") (pinfunction "40_40") (pintype "passive"))
    )
    (net (code "95") (name "unconnected-(U1-*SUSPEND-Pad11)") (class "Default")
      (node (ref "U1") (pin "11") (pinfunction "*SUSPEND_11") (pintype "passive"))
    )
    (net (code "96") (name "unconnected-(U1-CTS-Pad23)") (class "Default")
      (node (ref "U1") (pin "23") (pinfunction "CTS_23") (pintype "passive"))
    )
    (net (code "97") (name "unconnected-(U1-DCD-Pad1)") (class "Default")
      (node (ref "U1") (pin "1") (pinfunction "DCD_1") (pintype "passive"))
    )
    (net (code "98") (name "unconnected-(U1-DSR-Pad27)") (class "Default")
      (node (ref "U1") (pin "27") (pinfunction "DSR_27") (pintype "passive"))
    )
    (net (code "99") (name "unconnected-(U1-NC-Pad10)") (class "Default")
      (node (ref "U1") (pin "10") (pinfunction "NC_10") (pintype "passive"))
    )
    (net (code "100") (name "unconnected-(U1-NC-Pad13)") (class "Default")
      (node (ref "U1") (pin "13") (pinfunction "NC_13") (pintype "passive"))
    )
    (net (code "101") (name "unconnected-(U1-NC-Pad14)") (class "Default")
      (node (ref "U1") (pin "14") (pinfunction "NC_14") (pintype "passive"))
    )
    (net (code "102") (name "unconnected-(U1-NC-Pad15)") (class "Default")
      (node (ref "U1") (pin "15") (pinfunction "NC_15") (pintype "passive"))
    )
    (net (code "103") (name "unconnected-(U1-NC-Pad16)") (class "Default")
      (node (ref "U1") (pin "16") (pinfunction "NC_16") (pintype "passive"))
    )
    (net (code "104") (name "unconnected-(U1-NC-Pad17)") (class "Default")
      (node (ref "U1") (pin "17") (pinfunction "NC_17") (pintype "passive"))
    )
    (net (code "105") (name "unconnected-(U1-NC-Pad18)") (class "Default")
      (node (ref "U1") (pin "18") (pinfunction "NC_18") (pintype "passive"))
    )
    (net (code "106") (name "unconnected-(U1-NC-Pad19)") (class "Default")
      (node (ref "U1") (pin "19") (pinfunction "NC_19") (pintype "passive"))
    )
    (net (code "107") (name "unconnected-(U1-NC-Pad20)") (class "Default")
      (node (ref "U1") (pin "20") (pinfunction "NC_20") (pintype "passive"))
    )
    (net (code "108") (name "unconnected-(U1-NC-Pad21)") (class "Default")
      (node (ref "U1") (pin "21") (pinfunction "NC_21") (pintype "passive"))
    )
    (net (code "109") (name "unconnected-(U1-NC-Pad22)") (class "Default")
      (node (ref "U1") (pin "22") (pinfunction "NC_22") (pintype "passive"))
    )
    (net (code "110") (name "unconnected-(U1-RI-Pad2)") (class "Default")
      (node (ref "U1") (pin "2") (pinfunction "RI_2") (pintype "passive"))
    )
    (net (code "111") (name "unconnected-(U1-SUSPEND-Pad12)") (class "Default")
      (node (ref "U1") (pin "12") (pinfunction "SUSPEND_12") (pintype "passive"))
    )
    (net (code "112") (name "unconnected-(U1-VDD-Pad6)") (class "Default")
      (node (ref "U1") (pin "6") (pinfunction "VDD_6") (pintype "passive"))
    )
    (net (code "113") (name "unconnected-(U3-CAP1_NC-Pad48)") (class "Default")
      (node (ref "U3") (pin "48") (pinfunction "CAP1_NC_48") (pintype "passive"))
    )
    (net (code "114") (name "unconnected-(U3-CAP2_NC-Pad47)") (class "Default")
      (node (ref "U3") (pin "47") (pinfunction "CAP2_NC_47") (pintype "passive"))
    )
    (net (code "115") (name "unconnected-(U3-VDD_SDIO_NC-Pad26)") (class "Default")
      (node (ref "U3") (pin "26") (pinfunction "VDD_SDIO_NC_26") (pintype "passive"))
    )
    (net (code "116") (name "unconnected-(U3-XTAL_N_NC-Pad44)") (class "Default")
      (node (ref "U3") (pin "44") (pinfunction "XTAL_N_NC_44") (pintype "passive"))
    )
    (net (code "117") (name "unconnected-(U3-XTAL_P_NC-Pad45)") (class "Default")
      (node (ref "U3") (pin "45") (pinfunction "XTAL_P_NC_45") (pintype "passive"))
    )
    (net (code "118") (name "unconnected-(U4-A_CL-Pad7)") (class "Default")
      (node (ref "U4") (pin "7") (pinfunction "A_CL_7") (pintype "passive"))
    )
    (net (code "119") (name "unconnected-(U4-A_DA-Pad6)") (class "Default")
      (node (ref "U4") (pin "6") (pinfunction "A_DA_6") (pintype "passive"))
    )
    (net (code "120") (name "unconnected-(U4-CLKOUT-Pad22)") (class "Default")
      (node (ref "U4") (pin "22") (pinfunction "CLKOUT_22") (pintype "passive"))
    )
    (net (code "121") (name "unconnected-(U4-NC-Pad2)") (class "Default")
      (node (ref "U4") (pin "2") (pinfunction "NC_2") (pintype "passive"))
    )
    (net (code "122") (name "unconnected-(U4-NC-Pad3)") (class "Default")
      (node (ref "U4") (pin "3") (pinfunction "NC_3") (pintype "passive"))
    )
    (net (code "123") (name "unconnected-(U4-NC-Pad4)") (class "Default")
      (node (ref "U4") (pin "4") (pinfunction "NC_4") (pintype "passive"))
    )
    (net (code "124") (name "unconnected-(U4-NC-Pad5)") (class "Default")
      (node (ref "U4") (pin "5") (pinfunction "NC_5") (pintype "passive"))
    )
    (net (code "125") (name "unconnected-(U4-NC-Pad14)") (class "Default")
      (node (ref "U4") (pin "14") (pinfunction "NC_14") (pintype "passive"))
    )
    (net (code "126") (name "unconnected-(U4-NC-Pad15)") (class "Default")
      (node (ref "U4") (pin "15") (pinfunction "NC_15") (pintype "passive"))
    )
    (net (code "127") (name "unconnected-(U4-NC-Pad16)") (class "Default")
      (node (ref "U4") (pin "16") (pinfunction "NC_16") (pintype "passive"))
    )
    (net (code "128") (name "unconnected-(U4-NC-Pad17)") (class "Default")
      (node (ref "U4") (pin "17") (pinfunction "NC_17") (pintype "passive"))
    )
    (net (code "129") (name "unconnected-(U4-RESV-Pad19)") (class "Default")
      (node (ref "U4") (pin "19") (pinfunction "RESV_19") (pintype "passive"))
    )
    (net (code "130") (name "unconnected-(U4-RESV-Pad21)") (class "Default")
      (node (ref "U4") (pin "21") (pinfunction "RESV_21") (pintype "passive"))
    )
    (net (code "131") (name "unconnected-(U5-NC-Pad5)") (class "Default")
      (node (ref "U5") (pin "5") (pinfunction "NC_5") (pintype "passive"))
    )
    (net (code "132") (name "unconnected-(U5-NC-Pad8)") (class "Default")
      (node (ref "U5") (pin "8") (pinfunction "NC_8") (pintype "passive"))
    )
    (net (code "133") (name "unconnected-(USB1-RX1+-PadB11)") (class "Default")
      (node (ref "USB1") (pin "B11") (pinfunction "RX1+_B11") (pintype "passive"))
    )
    (net (code "134") (name "unconnected-(USB1-RX1--PadB10)") (class "Default")
      (node (ref "USB1") (pin "B10") (pinfunction "RX1-_B10") (pintype "passive"))
    )
    (net (code "135") (name "unconnected-(USB1-RX2+-PadA11)") (class "Default")
      (node (ref "USB1") (pin "A11") (pinfunction "RX2+_A11") (pintype "passive"))
    )
    (net (code "136") (name "unconnected-(USB1-RX2--PadA10)") (class "Default")
      (node (ref "USB1") (pin "A10") (pinfunction "RX2-_A10") (pintype "passive"))
    )
    (net (code "137") (name "unconnected-(USB1-SBU1-PadA8)") (class "Default")
      (node (ref "USB1") (pin "A8") (pinfunction "SBU1_A8") (pintype "passive"))
    )
    (net (code "138") (name "unconnected-(USB1-SBU2-PadB8)") (class "Default")
      (node (ref "USB1") (pin "B8") (pinfunction "SBU2_B8") (pintype "passive"))
    )
    (net (code "139") (name "unconnected-(USB1-TX1+-PadA2)") (class "Default")
      (node (ref "USB1") (pin "A2") (pinfunction "TX1+_A2") (pintype "passive"))
    )
    (net (code "140") (name "unconnected-(USB1-TX1--PadA3)") (class "Default")
      (node (ref "USB1") (pin "A3") (pinfunction "TX1-_A3") (pintype "passive"))
    )
    (net (code "141") (name "unconnected-(USB1-TX2+-PadB2)") (class "Default")
      (node (ref "USB1") (pin "B2") (pinfunction "TX2+_B2") (pintype "passive"))
    )
    (net (code "142") (name "unconnected-(USB1-TX2--PadB3)") (class "Default")
      (node (ref "USB1") (pin "B3") (pinfunction "TX2-_B3") (pintype "passive"))
    )
  )
)
